# MoodCue.net
KiCad netlist of a schematic drawn in EAGLE
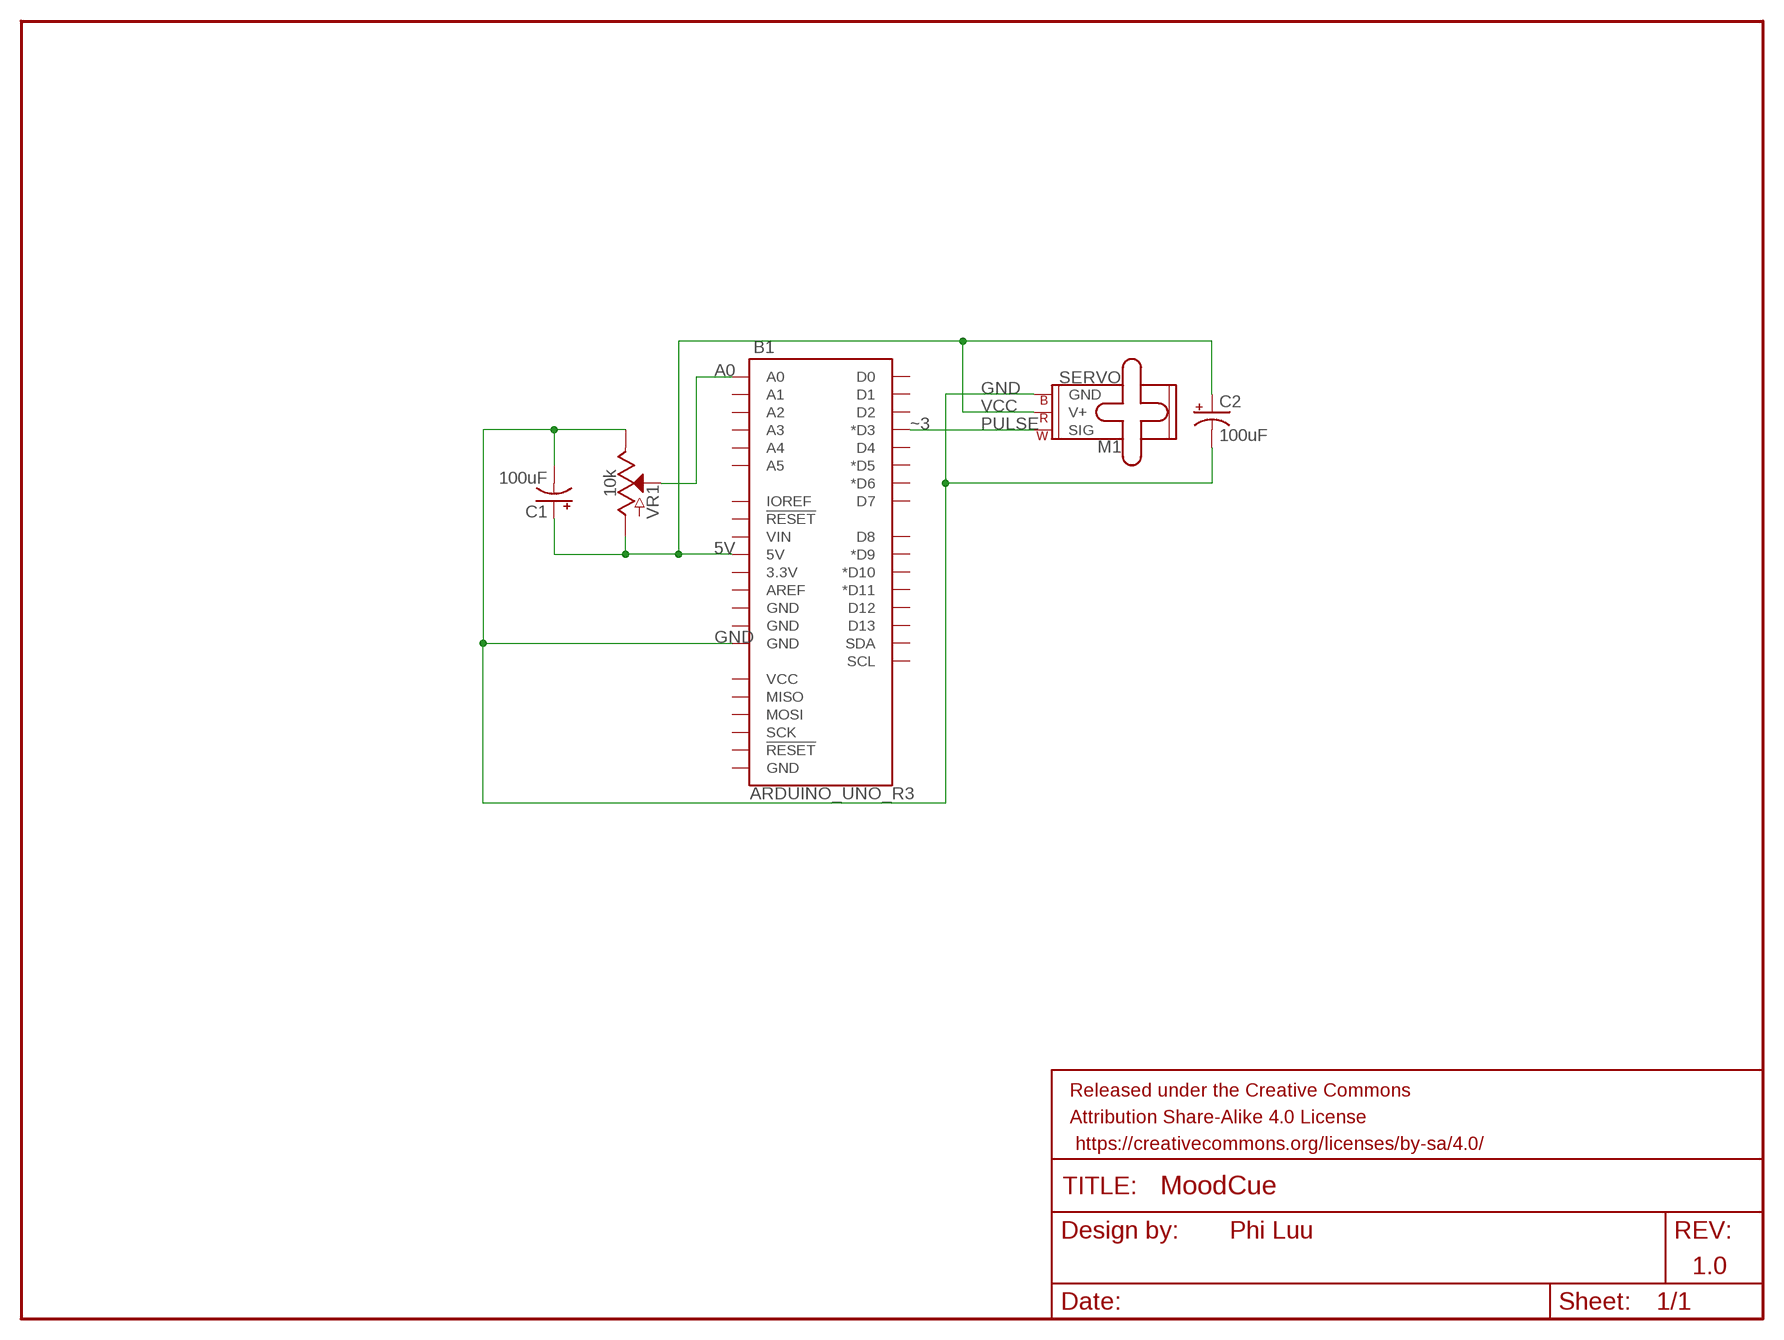
[diagram p0: schematic, sheet 1]

(export (version "E")
  (design (tool "Eeschema 10.0.6"))
  (components
    (comp (ref "B1")
      (value "ARDUINO_UNO_R3")
      (footprint "eagle-import:ARDUINO_R3")
      (libsource (lib "eagle-import") (part "ARDUINO_UNO_R3"))
    )
    (comp (ref "C1")
      (value "100uF")
      (footprint "eagle-import:CPOL-RADIAL-2.5MM-6.5MM")
      (libsource (lib "eagle-import") (part "100UF-POLAR-RADIAL-2.5MM-25V-20%"))
    )
    (comp (ref "C2")
      (value "100uF")
      (footprint "eagle-import:CPOL-RADIAL-2.5MM-6.5MM")
      (libsource (lib "eagle-import") (part "100UF-POLAR-RADIAL-2.5MM-25V-20%"))
    )
    (comp (ref "FRAME1")
      (value "FRAME-LETTER")
      (footprint "eagle-import:CREATIVE_COMMONS")
      (libsource (lib "eagle-import") (part "FRAME-LETTER"))
    )
    (comp (ref "M1")
      (value "SERVO")
      (footprint "eagle-import:1X03")
      (libsource (lib "eagle-import") (part "SERVO"))
    )
    (comp (ref "VR1")
      (value "10k")
      (footprint "eagle-import:POT-PTH-ALPS")
      (libsource (lib "eagle-import") (part "POTENTIOMETER-PTH-9MM-1/20W-20%"))
    )
  )
  (nets
    (net (code "1") (name "/5V") (class "Default")
      (node (ref "B1") (pin "5V") (pinfunction "5V_5V") (pintype "bidirectional"))
      (node (ref "C1") (pin "1") (pinfunction "+_1") (pintype "passive"))
      (node (ref "C2") (pin "1") (pinfunction "+_1") (pintype "passive"))
      (node (ref "M1") (pin "2") (pinfunction "V+_2") (pintype "bidirectional"))
      (node (ref "VR1") (pin "P$3") (pinfunction "A_P$3") (pintype "passive"))
    )
    (net (code "2") (name "/A0") (class "Default")
      (node (ref "B1") (pin "A0") (pinfunction "A0_A0") (pintype "bidirectional"))
      (node (ref "VR1") (pin "P$2") (pinfunction "S_P$2") (pintype "passive"))
    )
    (net (code "3") (name "/GND") (class "Default")
      (node (ref "B1") (pin "GND@2") (pinfunction "GND_GND@2") (pintype "bidirectional"))
      (node (ref "C1") (pin "2") (pinfunction "-_2") (pintype "passive"))
      (node (ref "C2") (pin "2") (pinfunction "-_2") (pintype "passive"))
      (node (ref "M1") (pin "3") (pinfunction "GND_3") (pintype "bidirectional"))
      (node (ref "VR1") (pin "P$1") (pinfunction "E_P$1") (pintype "passive"))
    )
    (net (code "4") (name "/~{3}") (class "Default")
      (node (ref "B1") (pin "D3") (pinfunction "*D3_D3") (pintype "bidirectional"))
      (node (ref "M1") (pin "1") (pinfunction "SIG_1") (pintype "bidirectional"))
    )
    (net (code "5") (name "unconnected-(B1-*D5-PadD5)") (class "Default")
      (node (ref "B1") (pin "D5") (pinfunction "*D5_D5") (pintype "bidirectional"))
    )
    (net (code "6") (name "unconnected-(B1-*D6-PadD6)") (class "Default")
      (node (ref "B1") (pin "D6") (pinfunction "*D6_D6") (pintype "bidirectional"))
    )
    (net (code "7") (name "unconnected-(B1-*D9-PadD9)") (class "Default")
      (node (ref "B1") (pin "D9") (pinfunction "*D9_D9") (pintype "bidirectional"))
    )
    (net (code "8") (name "unconnected-(B1-*D10-PadD10)") (class "Default")
      (node (ref "B1") (pin "D10") (pinfunction "*D10_D10") (pintype "bidirectional"))
    )
    (net (code "9") (name "unconnected-(B1-*D11-PadD11)") (class "Default")
      (node (ref "B1") (pin "D11") (pinfunction "*D11_D11") (pintype "bidirectional"))
    )
    (net (code "10") (name "unconnected-(B1-GND-PadGND@1)") (class "Default")
      (node (ref "B1") (pin "GND@1") (pinfunction "GND_GND@1") (pintype "bidirectional"))
    )
    (net (code "11") (name "unconnected-(B1-GND-PadGND@3)") (class "Default")
      (node (ref "B1") (pin "GND@3") (pinfunction "GND_GND@3") (pintype "bidirectional"))
    )
    (net (code "12") (name "unconnected-(B1-GND-PadGND@4)") (class "Default")
      (node (ref "B1") (pin "GND@4") (pinfunction "GND_GND@4") (pintype "bidirectional"))
    )
    (net (code "13") (name "unconnected-(B1-Pad3.3V)") (class "Default")
      (node (ref "B1") (pin "3.3V") (pinfunction "3.3V_3.3V") (pintype "bidirectional"))
    )
    (net (code "14") (name "unconnected-(B1-PadA1)") (class "Default")
      (node (ref "B1") (pin "A1") (pinfunction "A1_A1") (pintype "bidirectional"))
    )
    (net (code "15") (name "unconnected-(B1-PadA2)") (class "Default")
      (node (ref "B1") (pin "A2") (pinfunction "A2_A2") (pintype "bidirectional"))
    )
    (net (code "16") (name "unconnected-(B1-PadA3)") (class "Default")
      (node (ref "B1") (pin "A3") (pinfunction "A3_A3") (pintype "bidirectional"))
    )
    (net (code "17") (name "unconnected-(B1-PadA4)") (class "Default")
      (node (ref "B1") (pin "A4") (pinfunction "A4_A4") (pintype "bidirectional"))
    )
    (net (code "18") (name "unconnected-(B1-PadA5)") (class "Default")
      (node (ref "B1") (pin "A5") (pinfunction "A5_A5") (pintype "bidirectional"))
    )
    (net (code "19") (name "unconnected-(B1-PadAREF)") (class "Default")
      (node (ref "B1") (pin "AREF") (pinfunction "AREF_AREF") (pintype "bidirectional"))
    )
    (net (code "20") (name "unconnected-(B1-PadD0)") (class "Default")
      (node (ref "B1") (pin "D0") (pinfunction "D0_D0") (pintype "bidirectional"))
    )
    (net (code "21") (name "unconnected-(B1-PadD1)") (class "Default")
      (node (ref "B1") (pin "D1") (pinfunction "D1_D1") (pintype "bidirectional"))
    )
    (net (code "22") (name "unconnected-(B1-PadD2)") (class "Default")
      (node (ref "B1") (pin "D2") (pinfunction "D2_D2") (pintype "bidirectional"))
    )
    (net (code "23") (name "unconnected-(B1-PadD4)") (class "Default")
      (node (ref "B1") (pin "D4") (pinfunction "D4_D4") (pintype "bidirectional"))
    )
    (net (code "24") (name "unconnected-(B1-PadD7)") (class "Default")
      (node (ref "B1") (pin "D7") (pinfunction "D7_D7") (pintype "bidirectional"))
    )
    (net (code "25") (name "unconnected-(B1-PadD8)") (class "Default")
      (node (ref "B1") (pin "D8") (pinfunction "D8_D8") (pintype "bidirectional"))
    )
    (net (code "26") (name "unconnected-(B1-PadD12)") (class "Default")
      (node (ref "B1") (pin "D12") (pinfunction "D12_D12") (pintype "bidirectional"))
    )
    (net (code "27") (name "unconnected-(B1-PadD13)") (class "Default")
      (node (ref "B1") (pin "D13") (pinfunction "D13_D13") (pintype "bidirectional"))
    )
    (net (code "28") (name "unconnected-(B1-PadIOREF)") (class "Default")
      (node (ref "B1") (pin "IOREF") (pinfunction "IOREF_IOREF") (pintype "bidirectional"))
    )
    (net (code "29") (name "unconnected-(B1-PadMISO)") (class "Default")
      (node (ref "B1") (pin "MISO") (pinfunction "MISO_MISO") (pintype "bidirectional"))
    )
    (net (code "30") (name "unconnected-(B1-PadMOSI)") (class "Default")
      (node (ref "B1") (pin "MOSI") (pinfunction "MOSI_MOSI") (pintype "bidirectional"))
    )
    (net (code "31") (name "unconnected-(B1-PadSCK)") (class "Default")
      (node (ref "B1") (pin "SCK") (pinfunction "SCK_SCK") (pintype "bidirectional"))
    )
    (net (code "32") (name "unconnected-(B1-PadSCL)") (class "Default")
      (node (ref "B1") (pin "SCL") (pinfunction "SCL_SCL") (pintype "bidirectional"))
    )
    (net (code "33") (name "unconnected-(B1-PadSDA)") (class "Default")
      (node (ref "B1") (pin "SDA") (pinfunction "SDA_SDA") (pintype "bidirectional"))
    )
    (net (code "34") (name "unconnected-(B1-PadVCC)") (class "Default")
      (node (ref "B1") (pin "VCC") (pinfunction "VCC_VCC") (pintype "bidirectional"))
    )
    (net (code "35") (name "unconnected-(B1-PadVIN)") (class "Default")
      (node (ref "B1") (pin "VIN") (pinfunction "VIN_VIN") (pintype "bidirectional"))
    )
    (net (code "36") (name "unconnected-(B1-~{RESET}-PadRESET@1)") (class "Default")
      (node (ref "B1") (pin "RESET@1") (pinfunction "~{RESET}_RESET@1") (pintype "bidirectional"))
    )
    (net (code "37") (name "unconnected-(B1-~{RESET}-PadRESET@2)") (class "Default")
      (node (ref "B1") (pin "RESET@2") (pinfunction "~{RESET}_RESET@2") (pintype "bidirectional"))
    )
  )
)
